# V2_0.net
KiCad netlist of a schematic drawn in Altium Designer
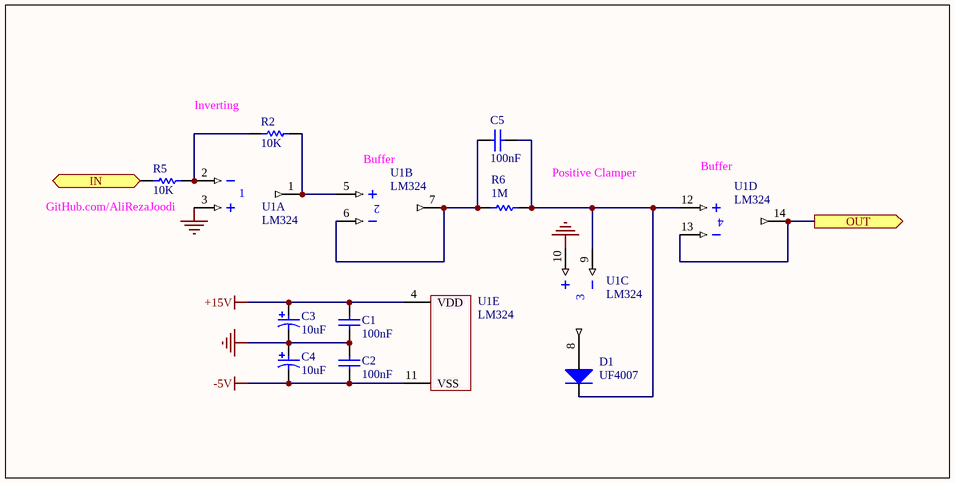
[diagram p0: V2.0.SchDoc]

(export (version "E")
  (design (tool "Eeschema 10.0.6"))
  (components
    (comp (ref "C1")
      (value "100nF")
      (footprint "CAPNTO2.54-3.05x1.78A")
      (description "Capacitor")
      (fields
        (field (name "MANUFACTURER") "Generic Components")
        (field (name "Comment") "Cap")
        (field (name "PUBLISHER") "Altium Limited")
      )
      (libsource (lib "Miscellaneous Devices") (part "Cap"))
    )
    (comp (ref "C2")
      (value "100nF")
      (footprint "CAPNTO2.54-3.05x1.78A")
      (description "Capacitor")
      (fields
        (field (name "MANUFACTURER") "Generic Components")
        (field (name "Comment") "Cap")
        (field (name "PUBLISHER") "Altium Limited")
      )
      (libsource (lib "Miscellaneous Devices") (part "Cap"))
    )
    (comp (ref "C3")
      (value "10uF")
      (footprint "C_THD_EL_(P2.54-D6-H11)")
      (description "Capacitor, Electrolytic")
      (libsource (lib "Passive") (part "Capacitor_Electrolytic"))
    )
    (comp (ref "C4")
      (value "10uF")
      (footprint "C_THD_EL_(P2.54-D6-H11)")
      (description "Capacitor, Electrolytic")
      (libsource (lib "Passive") (part "Capacitor_Electrolytic"))
    )
    (comp (ref "C5")
      (value "100nF")
      (footprint "CAPNTO2.54-3.05x1.78A")
      (description "Capacitor")
      (fields (field (name "MANUFACTURER") "Generic Components") (field (name "PUBLISHER") "Altium Limited"))
      (libsource (lib "Miscellaneous Devices") (part "Cap"))
    )
    (comp (ref "D1")
      (value "UF4007")
      (footprint "DIODE-0.4")
      (description "Default Diode")
      (fields (field (name "MANUFACTURER") "Generic Components") (field (name "PUBLISHER") "Altium Limited"))
      (libsource (lib "Miscellaneous Devices") (part "Diode"))
    )
    (comp (ref "R2")
      (value "10K")
      (footprint "AXIAL-0.4")
      (description "Resistor")
      (fields (field (name "PUBLISHER") "Altium Limited"))
      (libsource (lib "Miscellaneous Devices") (part "Res1"))
    )
    (comp (ref "R5")
      (value "10K")
      (footprint "AXIAL-0.4")
      (description "Resistor")
      (fields (field (name "PUBLISHER") "Altium Limited"))
      (libsource (lib "Miscellaneous Devices") (part "Res1"))
    )
    (comp (ref "R6")
      (value "1M")
      (footprint "AXIAL-0.4")
      (description "Resistor")
      (fields (field (name "PUBLISHER") "Altium Limited"))
      (libsource (lib "Miscellaneous Devices") (part "Res1"))
    )
    (comp (ref "U1")
      (value "LM324")
      (footprint "646-06")
      (description "Quad Low-Power Operational Amplifier")
      (fields (field (name "PUBLISHER") "Altium Limited"))
      (libsource (lib "") (part "LM324_1"))
    )
  )
  (nets
    (net (code "1") (name "+15V") (class "Default")
      (node (ref "C1") (pin "1") (pinfunction "1_1") (pintype "passive"))
      (node (ref "C3") (pin "1") (pinfunction "1_1") (pintype "passive"))
      (node (ref "U1") (pin "4") (pinfunction "VDD_4") (pintype "passive"))
    )
    (net (code "2") (name "-5V") (class "Default")
      (node (ref "C2") (pin "2") (pinfunction "2_2") (pintype "passive"))
      (node (ref "C4") (pin "2") (pinfunction "2_2") (pintype "passive"))
      (node (ref "U1") (pin "11") (pinfunction "VSS_11") (pintype "power_in"))
    )
    (net (code "3") (name "/IN") (class "Default")
      (node (ref "R5") (pin "2") (pinfunction "2_2") (pintype "passive"))
    )
    (net (code "4") (name "/OUT") (class "Default")
      (node (ref "U1") (pin "13") (pinfunction "IN-_13") (pintype "input"))
      (node (ref "U1") (pin "14") (pinfunction "OUT_14") (pintype "output"))
    )
    (net (code "5") (name "GND") (class "Default")
      (node (ref "C1") (pin "2") (pinfunction "2_2") (pintype "passive"))
      (node (ref "C2") (pin "1") (pinfunction "1_1") (pintype "passive"))
      (node (ref "C3") (pin "2") (pinfunction "2_2") (pintype "passive"))
      (node (ref "C4") (pin "1") (pinfunction "1_1") (pintype "passive"))
      (node (ref "U1") (pin "10") (pinfunction "IN+_10") (pintype "input"))
      (node (ref "U1") (pin "3") (pinfunction "IN+_3") (pintype "input"))
    )
    (net (code "6") (name "Net-(D1-A)") (class "Default")
      (node (ref "D1") (pin "1") (pinfunction "A_1") (pintype "passive"))
      (node (ref "U1") (pin "8") (pinfunction "OUT_8") (pintype "output"))
    )
    (net (code "7") (name "Net-(D1-K)") (class "Default")
      (node (ref "C5") (pin "1") (pinfunction "1_1") (pintype "passive"))
      (node (ref "D1") (pin "2") (pinfunction "K_2") (pintype "passive"))
      (node (ref "R6") (pin "1") (pinfunction "1_1") (pintype "passive"))
      (node (ref "U1") (pin "12") (pinfunction "IN+_12") (pintype "input"))
      (node (ref "U1") (pin "9") (pinfunction "IN-_9") (pintype "input"))
    )
    (net (code "8") (name "Net-(U1A-IN-)") (class "Default")
      (node (ref "R2") (pin "1") (pinfunction "1_1") (pintype "passive"))
      (node (ref "R5") (pin "1") (pinfunction "1_1") (pintype "passive"))
      (node (ref "U1") (pin "2") (pinfunction "IN-_2") (pintype "input"))
    )
    (net (code "9") (name "Net-(U1A-OUT)") (class "Default")
      (node (ref "R2") (pin "2") (pinfunction "2_2") (pintype "passive"))
      (node (ref "U1") (pin "1") (pinfunction "OUT_1") (pintype "output"))
      (node (ref "U1") (pin "5") (pinfunction "IN+_5") (pintype "input"))
    )
    (net (code "10") (name "Net-(U1B-IN-)") (class "Default")
      (node (ref "C5") (pin "2") (pinfunction "2_2") (pintype "passive"))
      (node (ref "R6") (pin "2") (pinfunction "2_2") (pintype "passive"))
      (node (ref "U1") (pin "6") (pinfunction "IN-_6") (pintype "input"))
      (node (ref "U1") (pin "7") (pinfunction "OUT_7") (pintype "output"))
    )
  )
)
